# xenon_mini.net
KiCad netlist of a schematic drawn in EAGLE
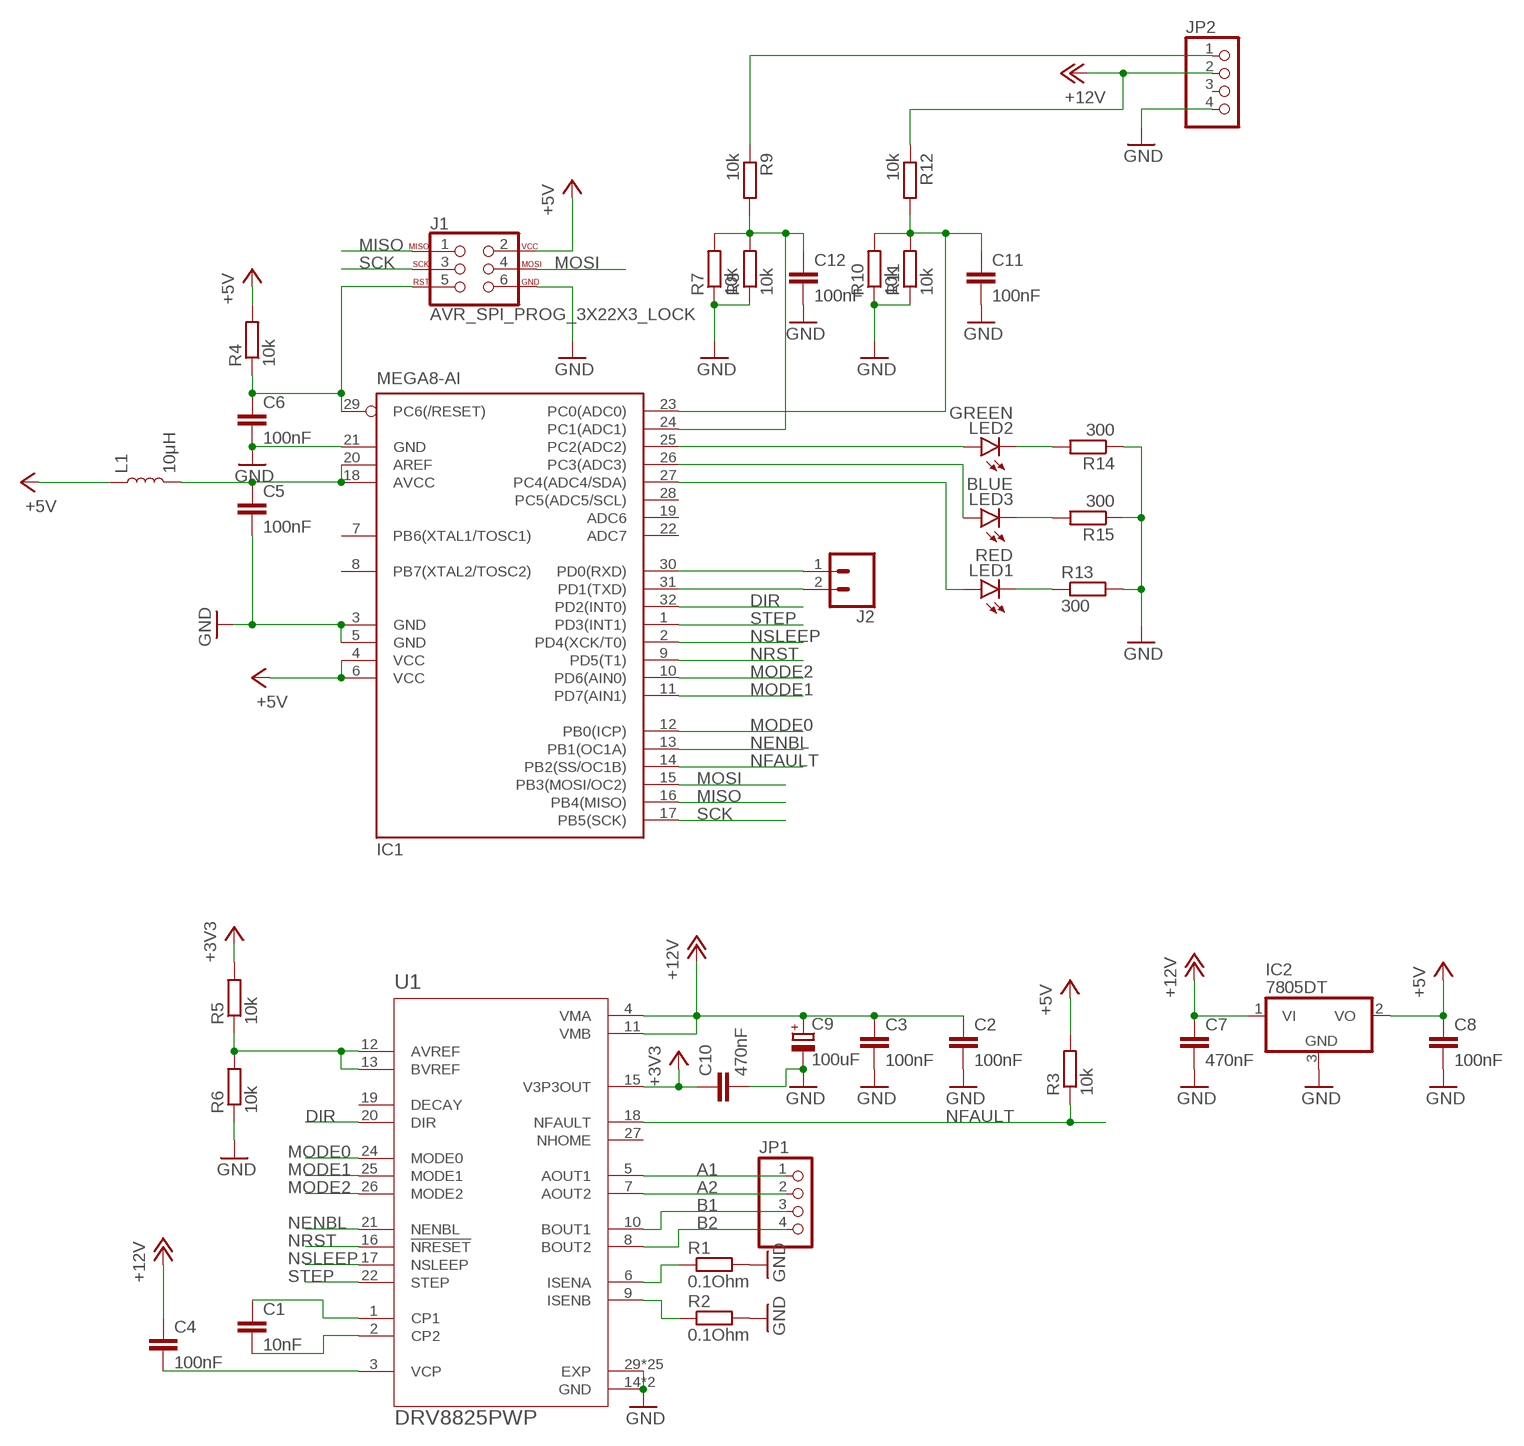
[diagram p0: schematic, sheet 1]

(export (version "E")
  (design (tool "Eeschema 10.0.6"))
  (components
    (comp (ref "C1")
      (value "10nF")
      (footprint "eagle-import:C0603")
      (libsource (lib "eagle-import") (part "C-EUC0603"))
    )
    (comp (ref "C2")
      (value "100nF")
      (footprint "eagle-import:C0603")
      (libsource (lib "eagle-import") (part "C-EUC0603"))
    )
    (comp (ref "C3")
      (value "100nF")
      (footprint "eagle-import:C0603")
      (libsource (lib "eagle-import") (part "C-EUC0603"))
    )
    (comp (ref "C4")
      (value "100nF")
      (footprint "eagle-import:C0603")
      (libsource (lib "eagle-import") (part "C-EUC0603"))
    )
    (comp (ref "C5")
      (value "100nF")
      (footprint "eagle-import:C0603")
      (libsource (lib "eagle-import") (part "C-EUC0603"))
    )
    (comp (ref "C6")
      (value "100nF")
      (footprint "eagle-import:C0603")
      (libsource (lib "eagle-import") (part "C-EUC0603"))
    )
    (comp (ref "C7")
      (value "470nF")
      (footprint "eagle-import:C0603")
      (libsource (lib "eagle-import") (part "C-EUC0603"))
    )
    (comp (ref "C8")
      (value "100nF")
      (footprint "eagle-import:C0603")
      (libsource (lib "eagle-import") (part "C-EUC0603"))
    )
    (comp (ref "C9")
      (value "100uF")
      (footprint "eagle-import:UD-6,3X7,7_NICHICON")
      (libsource (lib "eagle-import") (part "CPOL-EUUD-6,3X7,7"))
    )
    (comp (ref "C10")
      (value "470nF")
      (footprint "eagle-import:C0603")
      (libsource (lib "eagle-import") (part "C-EUC0603"))
    )
    (comp (ref "C11")
      (value "100nF")
      (footprint "eagle-import:C0603")
      (libsource (lib "eagle-import") (part "C-EUC0603"))
    )
    (comp (ref "C12")
      (value "100nF")
      (footprint "eagle-import:C0603")
      (libsource (lib "eagle-import") (part "C-EUC0603"))
    )
    (comp (ref "IC1")
      (value "MEGA8-AI")
      (footprint "eagle-import:TQFP32-08")
      (fields (field (name "MPN") "ATMEGA8-16AU"))
      (libsource (lib "eagle-import") (part "MEGA8-AI"))
    )
    (comp (ref "IC2")
      (value "7805DT")
      (footprint "eagle-import:TO252")
      (libsource (lib "eagle-import") (part "78DT05"))
    )
    (comp (ref "J1")
      (value "AVR_SPI_PROG_3X22X3_LOCK")
      (footprint "eagle-import:2X3_LOCK")
      (libsource (lib "eagle-import") (part "AVR_SPI_PROG_3X22X3_LOCK"))
    )
    (comp (ref "J2")
      (value "CONN_02LOCK")
      (footprint "eagle-import:1X02_LOCK")
      (libsource (lib "eagle-import") (part "CONN_02LOCK"))
    )
    (comp (ref "JP1")
      (value "PINHD-1X4")
      (footprint "eagle-import:1X04")
      (libsource (lib "eagle-import") (part "PINHD-1X4"))
    )
    (comp (ref "JP2")
      (value "PINHD-1X4")
      (footprint "eagle-import:1X04")
      (libsource (lib "eagle-import") (part "PINHD-1X4"))
    )
    (comp (ref "L1")
      (value "10μH")
      (footprint "eagle-import:0805")
      (libsource (lib "eagle-import") (part "10μH_SHIELDED_INDUCTOR0805"))
    )
    (comp (ref "LED1")
      (value "RED")
      (footprint "eagle-import:SML0603")
      (libsource (lib "eagle-import") (part "LEDSML0603"))
    )
    (comp (ref "LED2")
      (value "GREEN")
      (footprint "eagle-import:SML0603")
      (libsource (lib "eagle-import") (part "LEDSML0603"))
    )
    (comp (ref "LED3")
      (value "BLUE")
      (footprint "eagle-import:SML0603")
      (libsource (lib "eagle-import") (part "LEDSML0603"))
    )
    (comp (ref "R1")
      (value "0.1Ohm")
      (footprint "eagle-import:R1206")
      (libsource (lib "eagle-import") (part "R-EU_R1206"))
    )
    (comp (ref "R2")
      (value "0.1Ohm")
      (footprint "eagle-import:R1206")
      (libsource (lib "eagle-import") (part "R-EU_R1206"))
    )
    (comp (ref "R3")
      (value "10k")
      (footprint "eagle-import:R0603")
      (libsource (lib "eagle-import") (part "R-EU_R0603"))
    )
    (comp (ref "R4")
      (value "10k")
      (footprint "eagle-import:R0603")
      (libsource (lib "eagle-import") (part "R-EU_R0603"))
    )
    (comp (ref "R5")
      (value "10k")
      (footprint "eagle-import:R0603")
      (libsource (lib "eagle-import") (part "R-EU_R0603"))
    )
    (comp (ref "R6")
      (value "10k")
      (footprint "eagle-import:R0603")
      (libsource (lib "eagle-import") (part "R-EU_R0603"))
    )
    (comp (ref "R7")
      (value "10k")
      (footprint "eagle-import:R0603")
      (libsource (lib "eagle-import") (part "R-EU_R0603"))
    )
    (comp (ref "R8")
      (value "10k")
      (footprint "eagle-import:R0603")
      (libsource (lib "eagle-import") (part "R-EU_R0603"))
    )
    (comp (ref "R9")
      (value "10k")
      (footprint "eagle-import:R0603")
      (libsource (lib "eagle-import") (part "R-EU_R0603"))
    )
    (comp (ref "R10")
      (value "10k")
      (footprint "eagle-import:R0603")
      (libsource (lib "eagle-import") (part "R-EU_R0603"))
    )
    (comp (ref "R11")
      (value "10k")
      (footprint "eagle-import:R0603")
      (libsource (lib "eagle-import") (part "R-EU_R0603"))
    )
    (comp (ref "R12")
      (value "10k")
      (footprint "eagle-import:R0603")
      (libsource (lib "eagle-import") (part "R-EU_R0603"))
    )
    (comp (ref "R13")
      (value "300")
      (footprint "eagle-import:R0603")
      (libsource (lib "eagle-import") (part "R-EU_R0603"))
    )
    (comp (ref "R14")
      (value "300")
      (footprint "eagle-import:R0603")
      (libsource (lib "eagle-import") (part "R-EU_R0603"))
    )
    (comp (ref "R15")
      (value "300")
      (footprint "eagle-import:R0603")
      (libsource (lib "eagle-import") (part "R-EU_R0603"))
    )
    (comp (ref "U1")
      (value "DRV8825PWP")
      (footprint "eagle-import:SOP65P640X120-29N")
      (fields (field (name "MF") "Texas Instruments"))
      (libsource (lib "eagle-import") (part "DRV8825PWP"))
    )
  )
  (nets
    (net (code "1") (name "+3V3") (class "Default")
      (node (ref "C10") (pin "1") (pinfunction "1_1") (pintype "passive"))
      (node (ref "R5") (pin "2") (pinfunction "2_2") (pintype "passive"))
      (node (ref "U1") (pin "15") (pinfunction "V3P3OUT_15") (pintype "output"))
    )
    (net (code "2") (name "+5V") (class "Default")
      (node (ref "C8") (pin "1") (pinfunction "1_1") (pintype "passive"))
      (node (ref "IC1") (pin "4") (pinfunction "VCC_4") (pintype "power_in"))
      (node (ref "IC1") (pin "6") (pinfunction "VCC_6") (pintype "power_in"))
      (node (ref "IC2") (pin "2") (pinfunction "VO_2") (pintype "passive"))
      (node (ref "J1") (pin "2") (pinfunction "2_2") (pintype "passive"))
      (node (ref "L1") (pin "1") (pinfunction "1_1") (pintype "passive"))
      (node (ref "R3") (pin "2") (pinfunction "2_2") (pintype "passive"))
      (node (ref "R4") (pin "2") (pinfunction "2_2") (pintype "passive"))
    )
    (net (code "3") (name "+12V") (class "Default")
      (node (ref "C2") (pin "1") (pinfunction "1_1") (pintype "passive"))
      (node (ref "C3") (pin "1") (pinfunction "1_1") (pintype "passive"))
      (node (ref "C4") (pin "1") (pinfunction "1_1") (pintype "passive"))
      (node (ref "C7") (pin "1") (pinfunction "1_1") (pintype "passive"))
      (node (ref "C9") (pin "+") (pinfunction "+_+") (pintype "passive"))
      (node (ref "IC2") (pin "1") (pinfunction "VI_1") (pintype "input"))
      (node (ref "JP2") (pin "2") (pinfunction "2_2") (pintype "passive"))
      (node (ref "R12") (pin "1") (pinfunction "1_1") (pintype "passive"))
      (node (ref "U1") (pin "11") (pinfunction "VMB_11") (pintype "power_in"))
      (node (ref "U1") (pin "4") (pinfunction "VMA_4") (pintype "power_in"))
    )
    (net (code "4") (name "/A1") (class "Default")
      (node (ref "JP1") (pin "1") (pinfunction "1_1") (pintype "passive"))
      (node (ref "U1") (pin "5") (pinfunction "AOUT1_5") (pintype "output"))
    )
    (net (code "5") (name "/A2") (class "Default")
      (node (ref "JP1") (pin "2") (pinfunction "2_2") (pintype "passive"))
      (node (ref "U1") (pin "7") (pinfunction "AOUT2_7") (pintype "output"))
    )
    (net (code "6") (name "/B1") (class "Default")
      (node (ref "JP1") (pin "3") (pinfunction "3_3") (pintype "passive"))
      (node (ref "U1") (pin "10") (pinfunction "BOUT1_10") (pintype "output"))
    )
    (net (code "7") (name "/B2") (class "Default")
      (node (ref "JP1") (pin "4") (pinfunction "4_4") (pintype "passive"))
      (node (ref "U1") (pin "8") (pinfunction "BOUT2_8") (pintype "output"))
    )
    (net (code "8") (name "/DIR") (class "Default")
      (node (ref "IC1") (pin "32") (pinfunction "PD2(INT0)_32") (pintype "bidirectional"))
      (node (ref "U1") (pin "20") (pinfunction "DIR_20") (pintype "input"))
    )
    (net (code "9") (name "/MISO") (class "Default")
      (node (ref "IC1") (pin "16") (pinfunction "PB4(MISO)_16") (pintype "bidirectional"))
      (node (ref "J1") (pin "1") (pinfunction "1_1") (pintype "passive"))
    )
    (net (code "10") (name "/MODE0") (class "Default")
      (node (ref "IC1") (pin "12") (pinfunction "PB0(ICP)_12") (pintype "bidirectional"))
      (node (ref "U1") (pin "24") (pinfunction "MODE0_24") (pintype "input"))
    )
    (net (code "11") (name "/MODE1") (class "Default")
      (node (ref "IC1") (pin "11") (pinfunction "PD7(AIN1)_11") (pintype "bidirectional"))
      (node (ref "U1") (pin "25") (pinfunction "MODE1_25") (pintype "input"))
    )
    (net (code "12") (name "/MODE2") (class "Default")
      (node (ref "IC1") (pin "10") (pinfunction "PD6(AIN0)_10") (pintype "bidirectional"))
      (node (ref "U1") (pin "26") (pinfunction "MODE2_26") (pintype "input"))
    )
    (net (code "13") (name "/MOSI") (class "Default")
      (node (ref "IC1") (pin "15") (pinfunction "PB3(MOSI/OC2)_15") (pintype "bidirectional"))
      (node (ref "J1") (pin "4") (pinfunction "4_4") (pintype "passive"))
    )
    (net (code "14") (name "/NENBL") (class "Default")
      (node (ref "IC1") (pin "13") (pinfunction "PB1(OC1A)_13") (pintype "bidirectional"))
      (node (ref "U1") (pin "21") (pinfunction "NENBL_21") (pintype "input"))
    )
    (net (code "15") (name "/NFAULT") (class "Default")
      (node (ref "IC1") (pin "14") (pinfunction "PB2(SS/OC1B)_14") (pintype "bidirectional"))
      (node (ref "R3") (pin "1") (pinfunction "1_1") (pintype "passive"))
      (node (ref "U1") (pin "18") (pinfunction "NFAULT_18") (pintype "output"))
    )
    (net (code "16") (name "/NRST") (class "Default")
      (node (ref "IC1") (pin "9") (pinfunction "PD5(T1)_9") (pintype "bidirectional"))
      (node (ref "U1") (pin "16") (pinfunction "~{NRESET}_16") (pintype "input"))
    )
    (net (code "17") (name "/NSLEEP") (class "Default")
      (node (ref "IC1") (pin "2") (pinfunction "PD4(XCK/T0)_2") (pintype "bidirectional"))
      (node (ref "U1") (pin "17") (pinfunction "NSLEEP_17") (pintype "input"))
    )
    (net (code "18") (name "/SCK") (class "Default")
      (node (ref "IC1") (pin "17") (pinfunction "PB5(SCK)_17") (pintype "bidirectional"))
      (node (ref "J1") (pin "3") (pinfunction "3_3") (pintype "passive"))
    )
    (net (code "19") (name "/STEP") (class "Default")
      (node (ref "IC1") (pin "1") (pinfunction "PD3(INT1)_1") (pintype "bidirectional"))
      (node (ref "U1") (pin "22") (pinfunction "STEP_22") (pintype "input"))
    )
    (net (code "20") (name "GND") (class "Default")
      (node (ref "C10") (pin "2") (pinfunction "2_2") (pintype "passive"))
      (node (ref "C11") (pin "2") (pinfunction "2_2") (pintype "passive"))
      (node (ref "C12") (pin "2") (pinfunction "2_2") (pintype "passive"))
      (node (ref "C2") (pin "2") (pinfunction "2_2") (pintype "passive"))
      (node (ref "C3") (pin "2") (pinfunction "2_2") (pintype "passive"))
      (node (ref "C5") (pin "2") (pinfunction "2_2") (pintype "passive"))
      (node (ref "C6") (pin "2") (pinfunction "2_2") (pintype "passive"))
      (node (ref "C7") (pin "2") (pinfunction "2_2") (pintype "passive"))
      (node (ref "C8") (pin "2") (pinfunction "2_2") (pintype "passive"))
      (node (ref "C9") (pin "-") (pinfunction "-_-") (pintype "passive"))
      (node (ref "IC1") (pin "21") (pinfunction "GND_21") (pintype "power_in"))
      (node (ref "IC1") (pin "3") (pinfunction "GND_3") (pintype "power_in"))
      (node (ref "IC1") (pin "5") (pinfunction "GND_5") (pintype "power_in"))
      (node (ref "IC2") (pin "3") (pinfunction "GND_3") (pintype "passive"))
      (node (ref "J1") (pin "6") (pinfunction "6_6") (pintype "passive"))
      (node (ref "JP2") (pin "4") (pinfunction "4_4") (pintype "passive"))
      (node (ref "R1") (pin "2") (pinfunction "2_2") (pintype "passive"))
      (node (ref "R10") (pin "1") (pinfunction "1_1") (pintype "passive"))
      (node (ref "R11") (pin "1") (pinfunction "1_1") (pintype "passive"))
      (node (ref "R13") (pin "2") (pinfunction "2_2") (pintype "passive"))
      (node (ref "R14") (pin "1") (pinfunction "1_1") (pintype "passive"))
      (node (ref "R15") (pin "1") (pinfunction "1_1") (pintype "passive"))
      (node (ref "R2") (pin "2") (pinfunction "2_2") (pintype "passive"))
      (node (ref "R6") (pin "1") (pinfunction "1_1") (pintype "passive"))
      (node (ref "R7") (pin "1") (pinfunction "1_1") (pintype "passive"))
      (node (ref "R8") (pin "1") (pinfunction "1_1") (pintype "passive"))
      (node (ref "U1") (pin "14") (pinfunction "GND_14") (pintype "power_in"))
      (node (ref "U1") (pin "28") (pinfunction "GND_28") (pintype "power_in"))
      (node (ref "U1") (pin "29") (pinfunction "EXP_29") (pintype "power_in"))
      (node (ref "U1") (pin "P1") (pinfunction "EXP_P1") (pintype "power_in"))
      (node (ref "U1") (pin "P10") (pinfunction "EXP_P10") (pintype "power_in"))
      (node (ref "U1") (pin "P11") (pinfunction "EXP_P11") (pintype "power_in"))
      (node (ref "U1") (pin "P12") (pinfunction "EXP_P12") (pintype "power_in"))
      (node (ref "U1") (pin "P13") (pinfunction "EXP_P13") (pintype "power_in"))
      (node (ref "U1") (pin "P14") (pinfunction "EXP_P14") (pintype "power_in"))
      (node (ref "U1") (pin "P15") (pinfunction "EXP_P15") (pintype "power_in"))
      (node (ref "U1") (pin "P16") (pinfunction "EXP_P16") (pintype "power_in"))
      (node (ref "U1") (pin "P17") (pinfunction "EXP_P17") (pintype "power_in"))
      (node (ref "U1") (pin "P18") (pinfunction "EXP_P18") (pintype "power_in"))
      (node (ref "U1") (pin "P19") (pinfunction "EXP_P19") (pintype "power_in"))
      (node (ref "U1") (pin "P2") (pinfunction "EXP_P2") (pintype "power_in"))
      (node (ref "U1") (pin "P20") (pinfunction "EXP_P20") (pintype "power_in"))
      (node (ref "U1") (pin "P21") (pinfunction "EXP_P21") (pintype "power_in"))
      (node (ref "U1") (pin "P22") (pinfunction "EXP_P22") (pintype "power_in"))
      (node (ref "U1") (pin "P23") (pinfunction "EXP_P23") (pintype "power_in"))
      (node (ref "U1") (pin "P24") (pinfunction "EXP_P24") (pintype "power_in"))
      (node (ref "U1") (pin "P3") (pinfunction "EXP_P3") (pintype "power_in"))
      (node (ref "U1") (pin "P4") (pinfunction "EXP_P4") (pintype "power_in"))
      (node (ref "U1") (pin "P5") (pinfunction "EXP_P5") (pintype "power_in"))
      (node (ref "U1") (pin "P6") (pinfunction "EXP_P6") (pintype "power_in"))
      (node (ref "U1") (pin "P7") (pinfunction "EXP_P7") (pintype "power_in"))
      (node (ref "U1") (pin "P8") (pinfunction "EXP_P8") (pintype "power_in"))
      (node (ref "U1") (pin "P9") (pinfunction "EXP_P9") (pintype "power_in"))
    )
    (net (code "21") (name "Net-(IC1-AREF)") (class "Default")
      (node (ref "C5") (pin "1") (pinfunction "1_1") (pintype "passive"))
      (node (ref "IC1") (pin "18") (pinfunction "AVCC_18") (pintype "power_in"))
      (node (ref "IC1") (pin "20") (pinfunction "AREF_20") (pintype "passive"))
      (node (ref "L1") (pin "2") (pinfunction "2_2") (pintype "passive"))
    )
    (net (code "22") (name "Net-(IC1-PC0(ADC0))") (class "Default")
      (node (ref "C11") (pin "1") (pinfunction "1_1") (pintype "passive"))
      (node (ref "IC1") (pin "23") (pinfunction "PC0(ADC0)_23") (pintype "bidirectional"))
      (node (ref "R10") (pin "2") (pinfunction "2_2") (pintype "passive"))
      (node (ref "R11") (pin "2") (pinfunction "2_2") (pintype "passive"))
      (node (ref "R12") (pin "2") (pinfunction "2_2") (pintype "passive"))
    )
    (net (code "23") (name "Net-(IC1-PC1(ADC1))") (class "Default")
      (node (ref "C12") (pin "1") (pinfunction "1_1") (pintype "passive"))
      (node (ref "IC1") (pin "24") (pinfunction "PC1(ADC1)_24") (pintype "bidirectional"))
      (node (ref "R7") (pin "2") (pinfunction "2_2") (pintype "passive"))
      (node (ref "R8") (pin "2") (pinfunction "2_2") (pintype "passive"))
      (node (ref "R9") (pin "2") (pinfunction "2_2") (pintype "passive"))
    )
    (net (code "24") (name "Net-(IC1-PC2(ADC2))") (class "Default")
      (node (ref "IC1") (pin "25") (pinfunction "PC2(ADC2)_25") (pintype "bidirectional"))
      (node (ref "LED2") (pin "A") (pinfunction "A_A") (pintype "passive"))
    )
    (net (code "25") (name "Net-(IC1-PC3(ADC3))") (class "Default")
      (node (ref "IC1") (pin "26") (pinfunction "PC3(ADC3)_26") (pintype "bidirectional"))
      (node (ref "LED3") (pin "A") (pinfunction "A_A") (pintype "passive"))
    )
    (net (code "26") (name "Net-(IC1-PC4(ADC4{slash}SDA))") (class "Default")
      (node (ref "IC1") (pin "27") (pinfunction "PC4(ADC4/SDA)_27") (pintype "bidirectional"))
      (node (ref "LED1") (pin "A") (pinfunction "A_A") (pintype "passive"))
    )
    (net (code "27") (name "Net-(IC1-PC6({slash}RESET))") (class "Default")
      (node (ref "C6") (pin "1") (pinfunction "1_1") (pintype "passive"))
      (node (ref "IC1") (pin "29") (pinfunction "PC6(/RESET)_29") (pintype "bidirectional"))
      (node (ref "J1") (pin "5") (pinfunction "5_5") (pintype "passive"))
      (node (ref "R4") (pin "1") (pinfunction "1_1") (pintype "passive"))
    )
    (net (code "28") (name "Net-(IC1-PD0(RXD))") (class "Default")
      (node (ref "IC1") (pin "30") (pinfunction "PD0(RXD)_30") (pintype "bidirectional"))
      (node (ref "J2") (pin "1") (pinfunction "1_1") (pintype "passive"))
    )
    (net (code "29") (name "Net-(IC1-PD1(TXD))") (class "Default")
      (node (ref "IC1") (pin "31") (pinfunction "PD1(TXD)_31") (pintype "bidirectional"))
      (node (ref "J2") (pin "2") (pinfunction "2_2") (pintype "passive"))
    )
    (net (code "30") (name "Net-(JP2-Pad1)") (class "Default")
      (node (ref "JP2") (pin "1") (pinfunction "1_1") (pintype "passive"))
      (node (ref "R9") (pin "1") (pinfunction "1_1") (pintype "passive"))
    )
    (net (code "31") (name "Net-(LED1-PadC)") (class "Default")
      (node (ref "LED1") (pin "C") (pinfunction "C_C") (pintype "passive"))
      (node (ref "R13") (pin "1") (pinfunction "1_1") (pintype "passive"))
    )
    (net (code "32") (name "Net-(LED2-PadC)") (class "Default")
      (node (ref "LED2") (pin "C") (pinfunction "C_C") (pintype "passive"))
      (node (ref "R14") (pin "2") (pinfunction "2_2") (pintype "passive"))
    )
    (net (code "33") (name "Net-(LED3-PadC)") (class "Default")
      (node (ref "LED3") (pin "C") (pinfunction "C_C") (pintype "passive"))
      (node (ref "R15") (pin "2") (pinfunction "2_2") (pintype "passive"))
    )
    (net (code "34") (name "Net-(U1-AVREF)") (class "Default")
      (node (ref "R5") (pin "1") (pinfunction "1_1") (pintype "passive"))
      (node (ref "R6") (pin "2") (pinfunction "2_2") (pintype "passive"))
      (node (ref "U1") (pin "12") (pinfunction "AVREF_12") (pintype "input"))
      (node (ref "U1") (pin "13") (pinfunction "BVREF_13") (pintype "input"))
    )
    (net (code "35") (name "Net-(U1-CP1)") (class "Default")
      (node (ref "C1") (pin "1") (pinfunction "1_1") (pintype "passive"))
      (node (ref "U1") (pin "1") (pinfunction "CP1_1") (pintype "bidirectional"))
    )
    (net (code "36") (name "Net-(U1-CP2)") (class "Default")
      (node (ref "C1") (pin "2") (pinfunction "2_2") (pintype "passive"))
      (node (ref "U1") (pin "2") (pinfunction "CP2_2") (pintype "bidirectional"))
    )
    (net (code "37") (name "Net-(U1-ISENA)") (class "Default")
      (node (ref "R1") (pin "1") (pinfunction "1_1") (pintype "passive"))
      (node (ref "U1") (pin "6") (pinfunction "ISENA_6") (pintype "bidirectional"))
    )
    (net (code "38") (name "Net-(U1-ISENB)") (class "Default")
      (node (ref "R2") (pin "1") (pinfunction "1_1") (pintype "passive"))
      (node (ref "U1") (pin "9") (pinfunction "ISENB_9") (pintype "bidirectional"))
    )
    (net (code "39") (name "Net-(U1-VCP)") (class "Default")
      (node (ref "C4") (pin "2") (pinfunction "2_2") (pintype "passive"))
      (node (ref "U1") (pin "3") (pinfunction "VCP_3") (pintype "bidirectional"))
    )
    (net (code "40") (name "unconnected-(IC1-ADC6-Pad19)") (class "Default")
      (node (ref "IC1") (pin "19") (pinfunction "ADC6_19") (pintype "bidirectional"))
    )
    (net (code "41") (name "unconnected-(IC1-ADC7-Pad22)") (class "Default")
      (node (ref "IC1") (pin "22") (pinfunction "ADC7_22") (pintype "bidirectional"))
    )
    (net (code "42") (name "unconnected-(IC1-PB6(XTAL1{slash}TOSC1)-Pad7)") (class "Default")
      (node (ref "IC1") (pin "7") (pinfunction "PB6(XTAL1/TOSC1)_7") (pintype "bidirectional"))
    )
    (net (code "43") (name "unconnected-(IC1-PB7(XTAL2{slash}TOSC2)-Pad8)") (class "Default")
      (node (ref "IC1") (pin "8") (pinfunction "PB7(XTAL2/TOSC2)_8") (pintype "bidirectional"))
    )
    (net (code "44") (name "unconnected-(IC1-PC5(ADC5{slash}SCL)-Pad28)") (class "Default")
      (node (ref "IC1") (pin "28") (pinfunction "PC5(ADC5/SCL)_28") (pintype "bidirectional"))
    )
    (net (code "45") (name "unconnected-(JP2-Pad3)") (class "Default")
      (node (ref "JP2") (pin "3") (pinfunction "3_3") (pintype "passive"))
    )
    (net (code "46") (name "unconnected-(U1-DECAY-Pad19)") (class "Default")
      (node (ref "U1") (pin "19") (pinfunction "DECAY_19") (pintype "input"))
    )
    (net (code "47") (name "unconnected-(U1-NHOME-Pad27)") (class "Default")
      (node (ref "U1") (pin "27") (pinfunction "NHOME_27") (pintype "output"))
    )
  )
)
